# MIC.net
KiCad netlist of a schematic drawn in Altium Designer
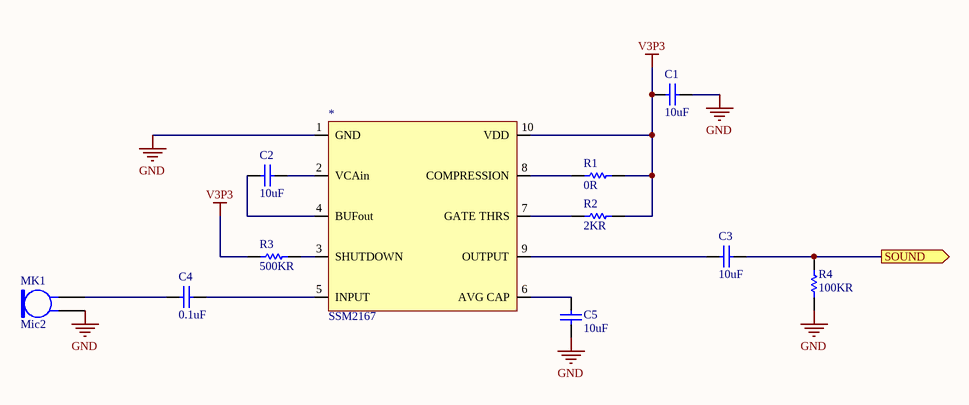
[diagram p0: MIC.SchDoc]

(export (version "E")
  (design (tool "Eeschema 10.0.6"))
  (components
    (comp (ref "*") (value "SSM2167") (libsource (lib "SCHLIB_Autobot") (part "SSM2167")))
    (comp (ref "C1")
      (value "10uF")
      (footprint "RAD-0.3")
      (description "Capacitor")
      (fields (field (name "PUBLISHER") "Altium Limited"))
      (libsource (lib "Miscellaneous Devices") (part "Cap"))
    )
    (comp (ref "C2")
      (value "10uF")
      (footprint "RAD-0.3")
      (description "Capacitor")
      (fields (field (name "PUBLISHER") "Altium Limited"))
      (libsource (lib "Miscellaneous Devices") (part "Cap"))
    )
    (comp (ref "C3")
      (value "10uF")
      (footprint "RAD-0.3")
      (description "Capacitor")
      (fields (field (name "PUBLISHER") "Altium Limited"))
      (libsource (lib "Miscellaneous Devices") (part "Cap"))
    )
    (comp (ref "C4")
      (value "0.1uF")
      (footprint "RAD-0.3")
      (description "Capacitor")
      (fields (field (name "PUBLISHER") "Altium Limited"))
      (libsource (lib "Miscellaneous Devices") (part "Cap"))
    )
    (comp (ref "C5")
      (value "10uF")
      (footprint "RAD-0.3")
      (description "Capacitor")
      (fields (field (name "PUBLISHER") "Altium Limited"))
      (libsource (lib "Miscellaneous Devices") (part "Cap"))
    )
    (comp (ref "MK1")
      (value "Mic2")
      (footprint "PIN2")
      (description "Microphone")
      (fields (field (name "PUBLISHER") "Altium Limited"))
      (libsource (lib "Miscellaneous Devices") (part "Mic2"))
    )
    (comp (ref "R1")
      (value "0R")
      (footprint "AXIAL-0.3")
      (description "Resistor")
      (fields (field (name "PUBLISHER") "Altium Limited"))
      (libsource (lib "Miscellaneous Devices") (part "Res1"))
    )
    (comp (ref "R2")
      (value "2KR")
      (footprint "AXIAL-0.3")
      (description "Resistor")
      (fields (field (name "PUBLISHER") "Altium Limited"))
      (libsource (lib "Miscellaneous Devices") (part "Res1"))
    )
    (comp (ref "R3")
      (value "500KR")
      (footprint "AXIAL-0.3")
      (description "Resistor")
      (fields (field (name "PUBLISHER") "Altium Limited"))
      (libsource (lib "Miscellaneous Devices") (part "Res1"))
    )
    (comp (ref "R4")
      (value "100KR")
      (footprint "AXIAL-0.3")
      (description "Resistor")
      (fields (field (name "PUBLISHER") "Altium Limited"))
      (libsource (lib "Miscellaneous Devices") (part "Res1"))
    )
  )
  (nets
    (net (code "1") (name "/SOUND") (class "Default")
      (node (ref "C3") (pin "1") (pinfunction "1_1") (pintype "passive"))
      (node (ref "R4") (pin "2") (pinfunction "2_2") (pintype "passive"))
    )
    (net (code "2") (name "GND") (class "Default")
      (node (ref "*") (pin "1") (pinfunction "GND_1") (pintype "passive"))
      (node (ref "C1") (pin "1") (pinfunction "1_1") (pintype "passive"))
      (node (ref "C5") (pin "2") (pinfunction "2_2") (pintype "passive"))
      (node (ref "MK1") (pin "1") (pinfunction "1_1") (pintype "passive"))
      (node (ref "R4") (pin "1") (pinfunction "1_1") (pintype "passive"))
    )
    (net (code "3") (name "Net-(*-AVG_CAP)") (class "Default")
      (node (ref "*") (pin "6") (pinfunction "AVG_CAP_6") (pintype "passive"))
      (node (ref "C5") (pin "1") (pinfunction "1_1") (pintype "passive"))
    )
    (net (code "4") (name "Net-(*-BUFout)") (class "Default")
      (node (ref "*") (pin "4") (pinfunction "BUFout_4") (pintype "passive"))
      (node (ref "C2") (pin "2") (pinfunction "2_2") (pintype "passive"))
    )
    (net (code "5") (name "Net-(*-COMPRESSION)") (class "Default")
      (node (ref "*") (pin "8") (pinfunction "COMPRESSION_8") (pintype "passive"))
      (node (ref "R1") (pin "2") (pinfunction "2_2") (pintype "passive"))
    )
    (net (code "6") (name "Net-(*-GATE_THRS)") (class "Default")
      (node (ref "*") (pin "7") (pinfunction "GATE_THRS_7") (pintype "passive"))
      (node (ref "R2") (pin "2") (pinfunction "2_2") (pintype "passive"))
    )
    (net (code "7") (name "Net-(*-INPUT)") (class "Default")
      (node (ref "*") (pin "5") (pinfunction "INPUT_5") (pintype "passive"))
      (node (ref "C4") (pin "2") (pinfunction "2_2") (pintype "passive"))
    )
    (net (code "8") (name "Net-(*-OUTPUT)") (class "Default")
      (node (ref "*") (pin "9") (pinfunction "OUTPUT_9") (pintype "passive"))
      (node (ref "C3") (pin "2") (pinfunction "2_2") (pintype "passive"))
    )
    (net (code "9") (name "Net-(*-SHUTDOWN)") (class "Default")
      (node (ref "*") (pin "3") (pinfunction "SHUTDOWN_3") (pintype "passive"))
      (node (ref "R3") (pin "1") (pinfunction "1_1") (pintype "passive"))
    )
    (net (code "10") (name "Net-(*-VCAin)") (class "Default")
      (node (ref "*") (pin "2") (pinfunction "VCAin_2") (pintype "passive"))
      (node (ref "C2") (pin "1") (pinfunction "1_1") (pintype "passive"))
    )
    (net (code "11") (name "Net-(C4-Pad1)") (class "Default")
      (node (ref "C4") (pin "1") (pinfunction "1_1") (pintype "passive"))
      (node (ref "MK1") (pin "2") (pinfunction "2_2") (pintype "passive"))
    )
    (net (code "12") (name "V3P3") (class "Default")
      (node (ref "*") (pin "10") (pinfunction "VDD_10") (pintype "passive"))
      (node (ref "C1") (pin "2") (pinfunction "2_2") (pintype "passive"))
      (node (ref "R1") (pin "1") (pinfunction "1_1") (pintype "passive"))
      (node (ref "R2") (pin "1") (pinfunction "1_1") (pintype "passive"))
      (node (ref "R3") (pin "2") (pinfunction "2_2") (pintype "passive"))
    )
  )
)
